# irio.net
KiCad netlist of a schematic drawn in EAGLE
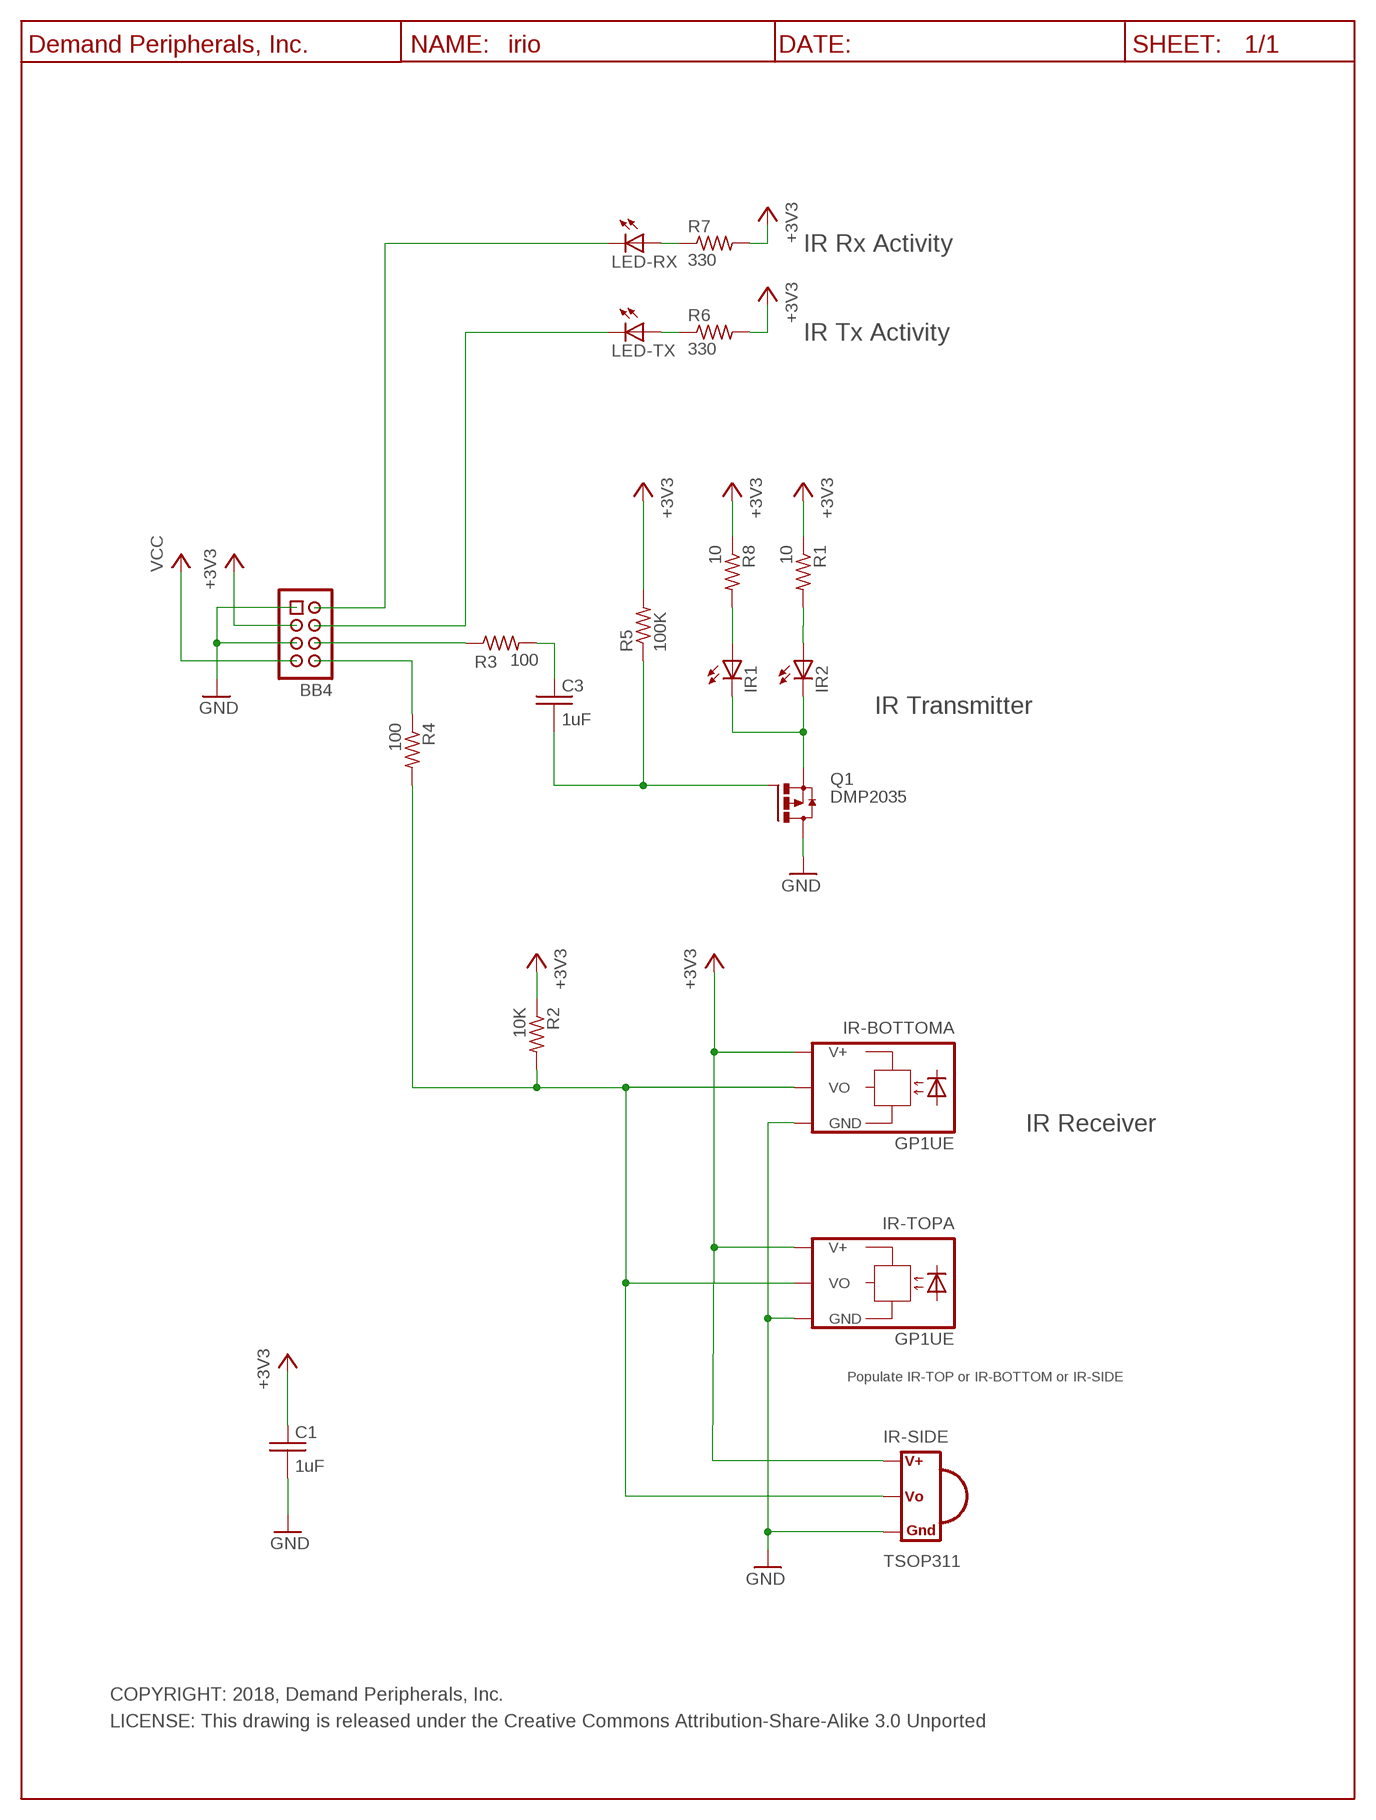
[diagram p0: schematic, sheet 1]

(export (version "E")
  (design (tool "Eeschema 10.0.6"))
  (components
    (comp (ref "BB4")
      (value "BB4-CON")
      (footprint "eagle-import:HDR-4X2")
      (libsource (lib "eagle-import") (part "HDR-4X2-SHR"))
    )
    (comp (ref "C1")
      (value "1uF")
      (footprint "eagle-import:C0603")
      (libsource (lib "eagle-import") (part "C1.0UF_C0603"))
    )
    (comp (ref "C3")
      (value "1uF")
      (footprint "eagle-import:C0603")
      (libsource (lib "eagle-import") (part "C1.0UF_C0603"))
    )
    (comp (ref "IR-BOTTOM")
      (value "GP1UE")
      (footprint "eagle-import:GP1UE")
      (libsource (lib "eagle-import") (part "GP1UE"))
    )
    (comp (ref "IR-SIDE")
      (value "TSOP311")
      (footprint "eagle-import:TSOP-IR-SIDE")
      (libsource (lib "eagle-import") (part "TSOP311"))
    )
    (comp (ref "IR-TOP")
      (value "GP1UE")
      (footprint "eagle-import:GP1UE")
      (libsource (lib "eagle-import") (part "GP1UE"))
    )
    (comp (ref "IR1")
      (value "LED-5MM-IR")
      (footprint "eagle-import:LED5MM")
      (libsource (lib "eagle-import") (part "LED-5MM-IR"))
    )
    (comp (ref "IR2")
      (value "LED-5MM-IR")
      (footprint "eagle-import:LED5MM")
      (libsource (lib "eagle-import") (part "LED-5MM-IR"))
    )
    (comp (ref "LED-RX")
      (value "LED")
      (footprint "eagle-import:LED5MM")
      (libsource (lib "eagle-import") (part "LED-5MM-GRN"))
    )
    (comp (ref "LED-TX")
      (value "LED")
      (footprint "eagle-import:LED5MM")
      (libsource (lib "eagle-import") (part "LED-5MM-RED"))
    )
    (comp (ref "Q1")
      (value "DMP2035")
      (footprint "eagle-import:SOT23")
      (libsource (lib "eagle-import") (part "DMP2035"))
    )
    (comp (ref "R1")
      (value "10")
      (footprint "eagle-import:R0603")
      (libsource (lib "eagle-import") (part "R10_R0603"))
    )
    (comp (ref "R2")
      (value "10K")
      (footprint "eagle-import:R0603")
      (libsource (lib "eagle-import") (part "R10K_R0603"))
    )
    (comp (ref "R3")
      (value "100")
      (footprint "eagle-import:R0603")
      (libsource (lib "eagle-import") (part "R100_R0603"))
    )
    (comp (ref "R4")
      (value "100")
      (footprint "eagle-import:R0603")
      (libsource (lib "eagle-import") (part "R100_R0603"))
    )
    (comp (ref "R5")
      (value "100K")
      (footprint "eagle-import:R0603")
      (libsource (lib "eagle-import") (part "R100K_R0603"))
    )
    (comp (ref "R6")
      (value "330")
      (footprint "eagle-import:R0603")
      (libsource (lib "eagle-import") (part "R330_R0603"))
    )
    (comp (ref "R7")
      (value "330")
      (footprint "eagle-import:R0603")
      (libsource (lib "eagle-import") (part "R330_R0603"))
    )
    (comp (ref "R8")
      (value "10")
      (footprint "eagle-import:R0603")
      (libsource (lib "eagle-import") (part "R10_R0603"))
    )
    (comp (ref "U$1")
      (value "DP_FRAME_P")
      (footprint "eagle-import:P_FRAME")
      (libsource (lib "eagle-import") (part "DP_FRAME_P"))
    )
  )
  (nets
    (net (code "1") (name "+3V3") (class "Default")
      (node (ref "BB4") (pin "3") (pinfunction "3_3") (pintype "passive"))
      (node (ref "C1") (pin "1") (pinfunction "1_1") (pintype "passive"))
      (node (ref "IR-BOTTOM") (pin "2") (pinfunction "V+_2") (pintype "power_in"))
      (node (ref "IR-SIDE") (pin "2") (pinfunction "V+_2") (pintype "power_in"))
      (node (ref "IR-TOP") (pin "2") (pinfunction "V+_2") (pintype "power_in"))
      (node (ref "R1") (pin "1") (pinfunction "1_1") (pintype "passive"))
      (node (ref "R2") (pin "1") (pinfunction "1_1") (pintype "passive"))
      (node (ref "R5") (pin "2") (pinfunction "2_2") (pintype "passive"))
      (node (ref "R6") (pin "2") (pinfunction "2_2") (pintype "passive"))
      (node (ref "R7") (pin "2") (pinfunction "2_2") (pintype "passive"))
      (node (ref "R8") (pin "1") (pinfunction "1_1") (pintype "passive"))
    )
    (net (code "2") (name "GND") (class "Default")
      (node (ref "BB4") (pin "1") (pinfunction "1_1") (pintype "passive"))
      (node (ref "BB4") (pin "5") (pinfunction "5_5") (pintype "passive"))
      (node (ref "C1") (pin "2") (pinfunction "2_2") (pintype "passive"))
      (node (ref "IR-BOTTOM") (pin "3") (pinfunction "GND_3") (pintype "power_in"))
      (node (ref "IR-SIDE") (pin "3") (pinfunction "GND_3") (pintype "power_in"))
      (node (ref "IR-TOP") (pin "3") (pinfunction "GND_3") (pintype "power_in"))
      (node (ref "Q1") (pin "3") (pinfunction "D_3") (pintype "passive"))
    )
    (net (code "3") (name "Net-(BB4-Pad2)") (class "Default")
      (node (ref "BB4") (pin "2") (pinfunction "2_2") (pintype "passive"))
      (node (ref "LED-RX") (pin "C") (pinfunction "C_C") (pintype "passive"))
    )
    (net (code "4") (name "Net-(BB4-Pad4)") (class "Default")
      (node (ref "BB4") (pin "4") (pinfunction "4_4") (pintype "passive"))
      (node (ref "LED-TX") (pin "C") (pinfunction "C_C") (pintype "passive"))
    )
    (net (code "5") (name "Net-(BB4-Pad6)") (class "Default")
      (node (ref "BB4") (pin "6") (pinfunction "6_6") (pintype "passive"))
      (node (ref "R3") (pin "1") (pinfunction "1_1") (pintype "passive"))
    )
    (net (code "6") (name "Net-(BB4-Pad8)") (class "Default")
      (node (ref "BB4") (pin "8") (pinfunction "8_8") (pintype "passive"))
      (node (ref "R4") (pin "1") (pinfunction "1_1") (pintype "passive"))
    )
    (net (code "7") (name "Net-(C3-Pad1)") (class "Default")
      (node (ref "C3") (pin "1") (pinfunction "1_1") (pintype "passive"))
      (node (ref "R3") (pin "2") (pinfunction "2_2") (pintype "passive"))
    )
    (net (code "8") (name "Net-(IR-BOTTOMA-VO)") (class "Default")
      (node (ref "IR-BOTTOM") (pin "1") (pinfunction "VO_1") (pintype "open_collector"))
      (node (ref "IR-SIDE") (pin "1") (pinfunction "VO_1") (pintype "open_collector"))
      (node (ref "IR-TOP") (pin "1") (pinfunction "VO_1") (pintype "open_collector"))
      (node (ref "R2") (pin "2") (pinfunction "2_2") (pintype "passive"))
      (node (ref "R4") (pin "2") (pinfunction "2_2") (pintype "passive"))
    )
    (net (code "9") (name "Net-(IR1-PadA)") (class "Default")
      (node (ref "IR1") (pin "A") (pinfunction "A_A") (pintype "passive"))
      (node (ref "R8") (pin "2") (pinfunction "2_2") (pintype "passive"))
    )
    (net (code "10") (name "Net-(IR2-PadA)") (class "Default")
      (node (ref "IR2") (pin "A") (pinfunction "A_A") (pintype "passive"))
      (node (ref "R1") (pin "2") (pinfunction "2_2") (pintype "passive"))
    )
    (net (code "11") (name "Net-(LED-RX-PadA)") (class "Default")
      (node (ref "LED-RX") (pin "A") (pinfunction "A_A") (pintype "passive"))
      (node (ref "R7") (pin "1") (pinfunction "1_1") (pintype "passive"))
    )
    (net (code "12") (name "Net-(LED-TX-PadA)") (class "Default")
      (node (ref "LED-TX") (pin "A") (pinfunction "A_A") (pintype "passive"))
      (node (ref "R6") (pin "1") (pinfunction "1_1") (pintype "passive"))
    )
    (net (code "13") (name "Net-(Q1-G)") (class "Default")
      (node (ref "C3") (pin "2") (pinfunction "2_2") (pintype "passive"))
      (node (ref "Q1") (pin "1") (pinfunction "G_1") (pintype "passive"))
      (node (ref "R5") (pin "1") (pinfunction "1_1") (pintype "passive"))
    )
    (net (code "14") (name "Net-(Q1-S)") (class "Default")
      (node (ref "IR1") (pin "C") (pinfunction "C_C") (pintype "passive"))
      (node (ref "IR2") (pin "C") (pinfunction "C_C") (pintype "passive"))
      (node (ref "Q1") (pin "2") (pinfunction "S_2") (pintype "passive"))
    )
    (net (code "15") (name "VCC") (class "Default")
      (node (ref "BB4") (pin "7") (pinfunction "7_7") (pintype "passive"))
    )
  )
)
